# LCDShield.net
KiCad netlist of a schematic drawn in EAGLE
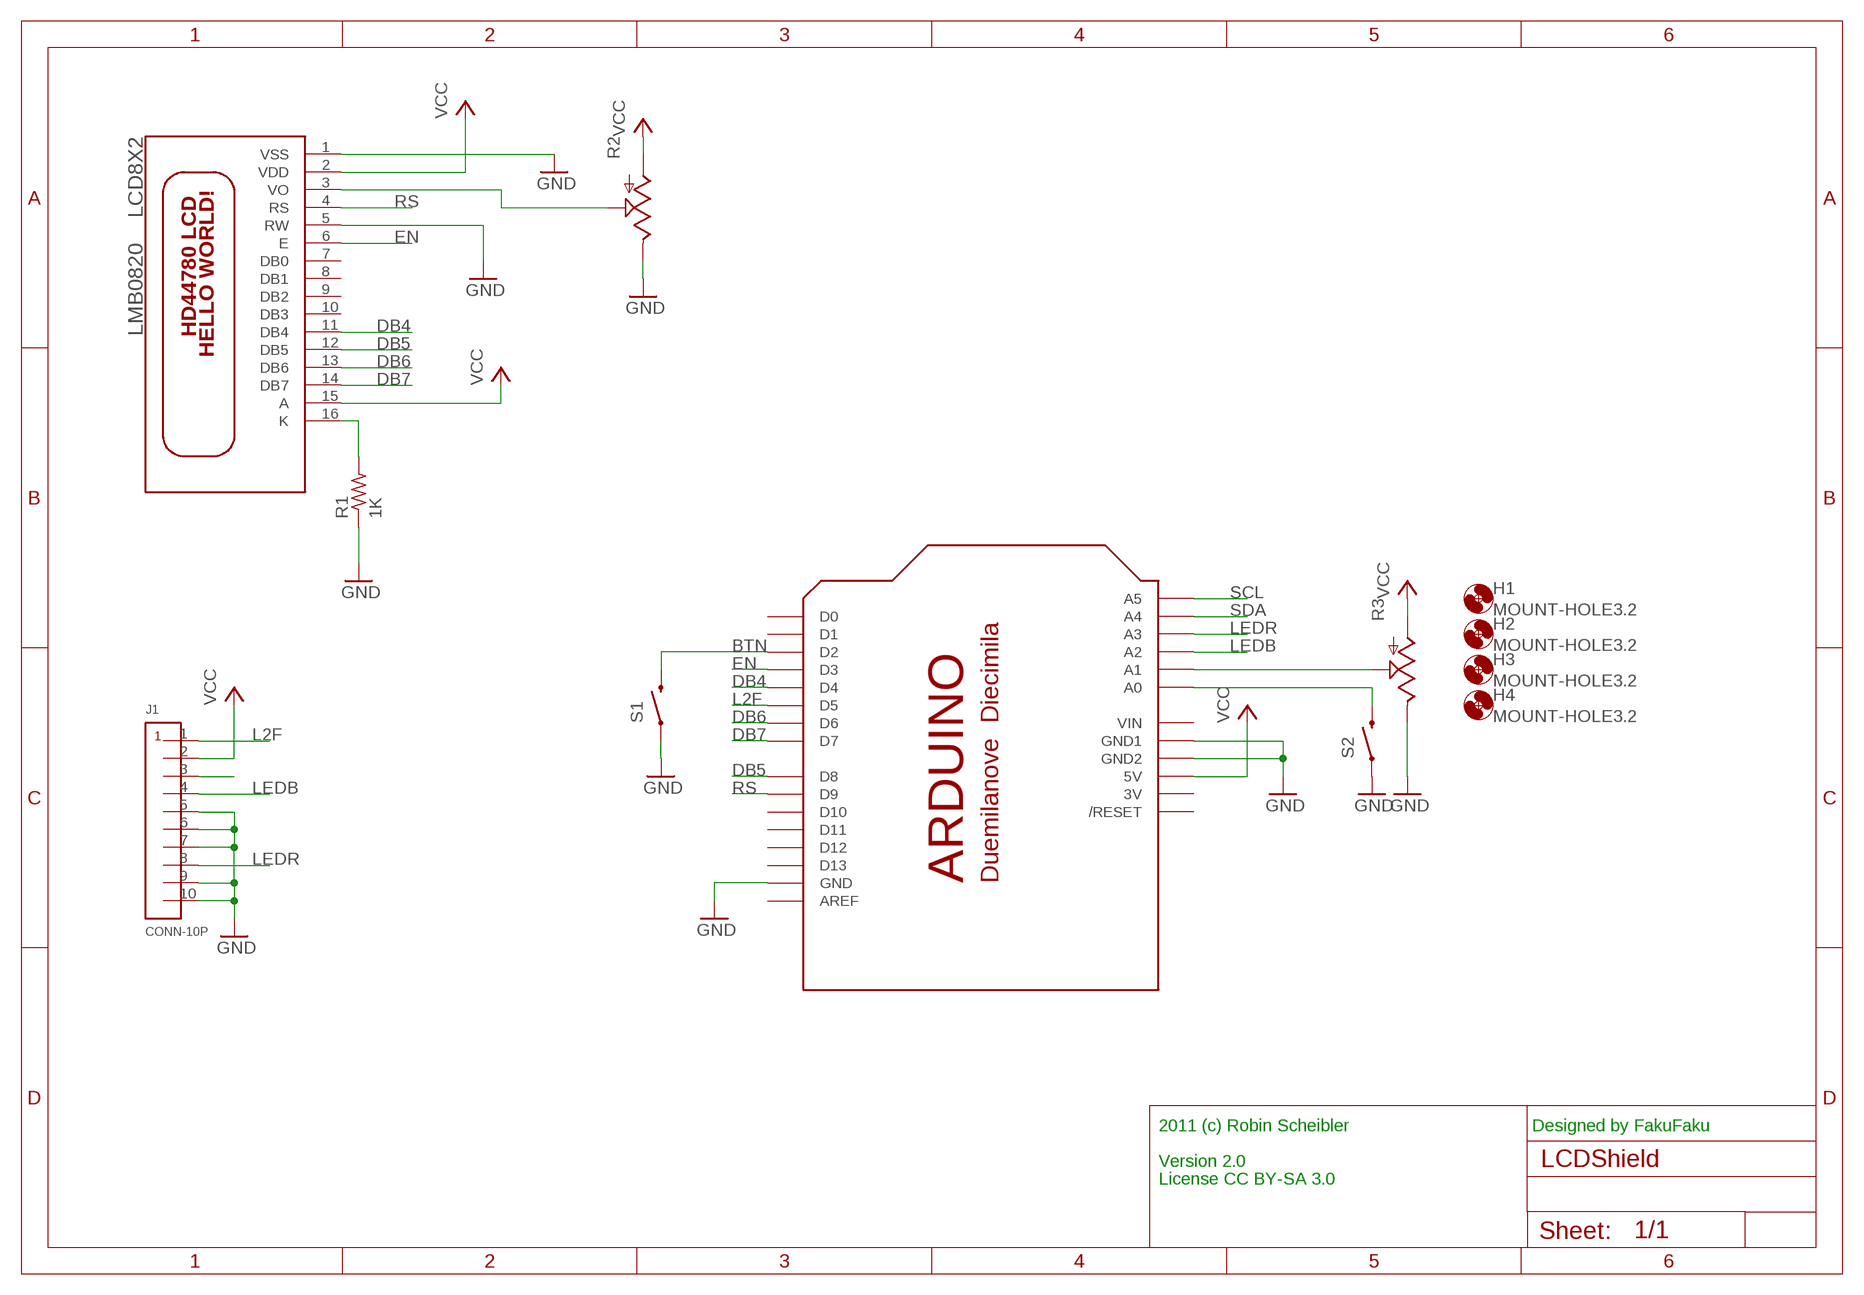
[diagram p0: schematic, sheet 1]

(export (version "E")
  (design (tool "Eeschema 10.0.6"))
  (components
    (comp (ref "H1")
      (value "MOUNT-HOLE3.2")
      (footprint "eagle-import:3,2")
      (libsource (lib "eagle-import") (part "MOUNT-HOLE3.2"))
    )
    (comp (ref "H2")
      (value "MOUNT-HOLE3.2")
      (footprint "eagle-import:3,2")
      (libsource (lib "eagle-import") (part "MOUNT-HOLE3.2"))
    )
    (comp (ref "H3")
      (value "MOUNT-HOLE3.2")
      (footprint "eagle-import:3,2")
      (libsource (lib "eagle-import") (part "MOUNT-HOLE3.2"))
    )
    (comp (ref "H4")
      (value "MOUNT-HOLE3.2")
      (footprint "eagle-import:3,2")
      (libsource (lib "eagle-import") (part "MOUNT-HOLE3.2"))
    )
    (comp (ref "J1")
      (value "CONN-10P")
      (footprint "eagle-import:MICROMATCH-10P-SMD")
      (libsource (lib "eagle-import") (part "CONN-10P"))
    )
    (comp (ref "LCD8X2")
      (value "LMB0820")
      (footprint "eagle-import:LMB0820")
      (libsource (lib "eagle-import") (part "LMB0820"))
    )
    (comp (ref "R1")
      (value "1K")
      (footprint "eagle-import:0207_10")
      (libsource (lib "eagle-import") (part "R-US_0207/10"))
    )
    (comp (ref "R2")
      (value "POTTRIM")
      (footprint "eagle-import:TRIM_POT")
      (libsource (lib "eagle-import") (part "POTTRIM"))
    )
    (comp (ref "R3")
      (value "POT")
      (footprint "eagle-import:ALPS_POT")
      (libsource (lib "eagle-import") (part "POT"))
    )
    (comp (ref "S1")
      (value "SWITCH-MOMENTARY-2PTH")
      (footprint "eagle-import:TACTILE-PTH")
      (libsource (lib "eagle-import") (part "SWITCH-MOMENTARY-2PTH"))
    )
    (comp (ref "S2")
      (value "SWITCH-MOMENTARY-2PTH")
      (footprint "eagle-import:TACTILE-PTH")
      (libsource (lib "eagle-import") (part "SWITCH-MOMENTARY-2PTH"))
    )
    (comp (ref "SHIELD")
      (value "ARDUINOSHIELD-PINS")
      (footprint "eagle-import:ARDUINO-PINS")
      (libsource (lib "eagle-import") (part "ARDUINOSHIELD-PINS"))
    )
  )
  (nets
    (net (code "1") (name "/3V") (class "Default")
      (node (ref "SHIELD") (pin "3V") (pinfunction "3V_3V") (pintype "power_in"))
    )
    (net (code "2") (name "/BTN") (class "Default")
      (node (ref "S1") (pin "3") (pinfunction "2_3") (pintype "passive"))
      (node (ref "SHIELD") (pin "D2") (pinfunction "D2_D2") (pintype "bidirectional"))
    )
    (net (code "3") (name "/DB4") (class "Default")
      (node (ref "LCD8X2") (pin "11") (pinfunction "DB4_11") (pintype "bidirectional"))
      (node (ref "SHIELD") (pin "D4") (pinfunction "D4_D4") (pintype "bidirectional"))
    )
    (net (code "4") (name "/DB5") (class "Default")
      (node (ref "LCD8X2") (pin "12") (pinfunction "DB5_12") (pintype "bidirectional"))
      (node (ref "SHIELD") (pin "D8") (pinfunction "D8_D8") (pintype "bidirectional"))
    )
    (net (code "5") (name "/DB6") (class "Default")
      (node (ref "LCD8X2") (pin "13") (pinfunction "DB6_13") (pintype "bidirectional"))
      (node (ref "SHIELD") (pin "D6") (pinfunction "D6_D6") (pintype "bidirectional"))
    )
    (net (code "6") (name "/DB7") (class "Default")
      (node (ref "LCD8X2") (pin "14") (pinfunction "DB7_14") (pintype "bidirectional"))
      (node (ref "SHIELD") (pin "D7") (pinfunction "D7_D7") (pintype "bidirectional"))
    )
    (net (code "7") (name "/EN") (class "Default")
      (node (ref "LCD8X2") (pin "6") (pinfunction "E_6") (pintype "input"))
      (node (ref "SHIELD") (pin "D3") (pinfunction "D3_D3") (pintype "bidirectional"))
    )
    (net (code "8") (name "/L2F") (class "Default")
      (node (ref "J1") (pin "1") (pinfunction "1_1") (pintype "bidirectional"))
      (node (ref "SHIELD") (pin "D5") (pinfunction "D5_D5") (pintype "bidirectional"))
    )
    (net (code "9") (name "/LEDB") (class "Default")
      (node (ref "J1") (pin "4") (pinfunction "4_4") (pintype "bidirectional"))
      (node (ref "SHIELD") (pin "A2") (pinfunction "A2_A2") (pintype "bidirectional"))
    )
    (net (code "10") (name "/LEDR") (class "Default")
      (node (ref "J1") (pin "8") (pinfunction "8_8") (pintype "bidirectional"))
      (node (ref "SHIELD") (pin "A3") (pinfunction "A3_A3") (pintype "bidirectional"))
    )
    (net (code "11") (name "/RS") (class "Default")
      (node (ref "LCD8X2") (pin "4") (pinfunction "RS_4") (pintype "input"))
      (node (ref "SHIELD") (pin "D9") (pinfunction "D9_D9") (pintype "bidirectional"))
    )
    (net (code "12") (name "/SCL") (class "Default")
      (node (ref "SHIELD") (pin "A5") (pinfunction "A5_A5") (pintype "bidirectional"))
    )
    (net (code "13") (name "/SDA") (class "Default")
      (node (ref "SHIELD") (pin "A4") (pinfunction "A4_A4") (pintype "bidirectional"))
    )
    (net (code "14") (name "/VIN") (class "Default")
      (node (ref "SHIELD") (pin "VIN") (pinfunction "VIN_VIN") (pintype "power_in"))
    )
    (net (code "15") (name "GND") (class "Default")
      (node (ref "J1") (pin "10") (pinfunction "10_10") (pintype "bidirectional"))
      (node (ref "J1") (pin "5") (pinfunction "5_5") (pintype "bidirectional"))
      (node (ref "J1") (pin "6") (pinfunction "6_6") (pintype "bidirectional"))
      (node (ref "J1") (pin "7") (pinfunction "7_7") (pintype "bidirectional"))
      (node (ref "J1") (pin "9") (pinfunction "9_9") (pintype "bidirectional"))
      (node (ref "LCD8X2") (pin "1") (pinfunction "VSS_1") (pintype "power_in"))
      (node (ref "LCD8X2") (pin "5") (pinfunction "RW_5") (pintype "input"))
      (node (ref "R1") (pin "1") (pinfunction "1_1") (pintype "passive"))
      (node (ref "R2") (pin "2") (pinfunction "E_2") (pintype "passive"))
      (node (ref "R3") (pin "P$1") (pinfunction "E_P$1") (pintype "passive"))
      (node (ref "S1") (pin "1") (pinfunction "1_1") (pintype "passive"))
      (node (ref "S2") (pin "1") (pinfunction "1_1") (pintype "passive"))
      (node (ref "SHIELD") (pin "GND") (pinfunction "GND_GND") (pintype "power_in"))
      (node (ref "SHIELD") (pin "GND1") (pinfunction "GND1_GND1") (pintype "power_in"))
      (node (ref "SHIELD") (pin "GND2") (pinfunction "GND2_GND2") (pintype "power_in"))
    )
    (net (code "16") (name "Net-(LCD8X2-K)") (class "Default")
      (node (ref "LCD8X2") (pin "16") (pinfunction "K_16") (pintype "input"))
      (node (ref "R1") (pin "2") (pinfunction "2_2") (pintype "passive"))
    )
    (net (code "17") (name "Net-(LCD8X2-VO)") (class "Default")
      (node (ref "LCD8X2") (pin "3") (pinfunction "VO_3") (pintype "input"))
      (node (ref "R2") (pin "1") (pinfunction "S_1") (pintype "passive"))
    )
    (net (code "18") (name "Net-(R3-S)") (class "Default")
      (node (ref "R3") (pin "P$2") (pinfunction "S_P$2") (pintype "passive"))
      (node (ref "SHIELD") (pin "A1") (pinfunction "A1_A1") (pintype "bidirectional"))
    )
    (net (code "19") (name "Net-(S2-2)") (class "Default")
      (node (ref "S2") (pin "3") (pinfunction "2_3") (pintype "passive"))
      (node (ref "SHIELD") (pin "A0") (pinfunction "A0_A0") (pintype "bidirectional"))
    )
    (net (code "20") (name "VCC") (class "Default")
      (node (ref "J1") (pin "2") (pinfunction "2_2") (pintype "bidirectional"))
      (node (ref "LCD8X2") (pin "15") (pinfunction "A_15") (pintype "input"))
      (node (ref "LCD8X2") (pin "2") (pinfunction "VDD_2") (pintype "power_in"))
      (node (ref "R2") (pin "3") (pinfunction "A_3") (pintype "passive"))
      (node (ref "R3") (pin "P$3") (pinfunction "A_P$3") (pintype "passive"))
      (node (ref "SHIELD") (pin "5V") (pinfunction "5V_5V") (pintype "power_in"))
    )
    (net (code "21") (name "unconnected-(J1-Pad3)") (class "Default")
      (node (ref "J1") (pin "3") (pinfunction "3_3") (pintype "bidirectional"))
    )
    (net (code "22") (name "unconnected-(LCD8X2-DB0-Pad7)") (class "Default")
      (node (ref "LCD8X2") (pin "7") (pinfunction "DB0_7") (pintype "bidirectional"))
    )
    (net (code "23") (name "unconnected-(LCD8X2-DB1-Pad8)") (class "Default")
      (node (ref "LCD8X2") (pin "8") (pinfunction "DB1_8") (pintype "bidirectional"))
    )
    (net (code "24") (name "unconnected-(LCD8X2-DB2-Pad9)") (class "Default")
      (node (ref "LCD8X2") (pin "9") (pinfunction "DB2_9") (pintype "bidirectional"))
    )
    (net (code "25") (name "unconnected-(LCD8X2-DB3-Pad10)") (class "Default")
      (node (ref "LCD8X2") (pin "10") (pinfunction "DB3_10") (pintype "bidirectional"))
    )
    (net (code "26") (name "unconnected-(SHIELD-PadAREF)") (class "Default")
      (node (ref "SHIELD") (pin "AREF") (pinfunction "AREF_AREF") (pintype "bidirectional"))
    )
    (net (code "27") (name "unconnected-(SHIELD-PadD0)") (class "Default")
      (node (ref "SHIELD") (pin "D0") (pinfunction "D0_D0") (pintype "bidirectional"))
    )
    (net (code "28") (name "unconnected-(SHIELD-PadD1)") (class "Default")
      (node (ref "SHIELD") (pin "D1") (pinfunction "D1_D1") (pintype "bidirectional"))
    )
    (net (code "29") (name "unconnected-(SHIELD-PadD10)") (class "Default")
      (node (ref "SHIELD") (pin "D10") (pinfunction "D10_D10") (pintype "bidirectional"))
    )
    (net (code "30") (name "unconnected-(SHIELD-PadD11)") (class "Default")
      (node (ref "SHIELD") (pin "D11") (pinfunction "D11_D11") (pintype "bidirectional"))
    )
    (net (code "31") (name "unconnected-(SHIELD-PadD12)") (class "Default")
      (node (ref "SHIELD") (pin "D12") (pinfunction "D12_D12") (pintype "bidirectional"))
    )
    (net (code "32") (name "unconnected-(SHIELD-PadD13)") (class "Default")
      (node (ref "SHIELD") (pin "D13") (pinfunction "D13_D13") (pintype "bidirectional"))
    )
    (net (code "33") (name "unconnected-(SHIELD-{slash}RESET-PadRESET)") (class "Default")
      (node (ref "SHIELD") (pin "RESET") (pinfunction "/RESET_RESET") (pintype "bidirectional"))
    )
  )
)
